# LM317.net
KiCad netlist of a schematic drawn in EAGLE
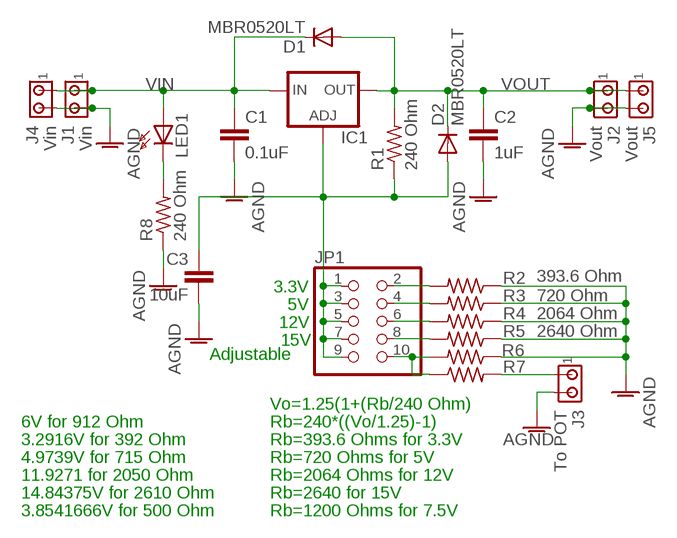
[diagram p0: schematic, sheet 1]

(export (version "E")
  (design (tool "Eeschema 10.0.6"))
  (components
    (comp (ref "C1")
      (value "0.1uF")
      (footprint "eagle-import:0805_PANASONIC")
      (libsource (lib "eagle-import") (part "0805_PANASONIC"))
    )
    (comp (ref "C2")
      (value "1uF")
      (footprint "eagle-import:0805_PANASONIC")
      (libsource (lib "eagle-import") (part "0805_PANASONIC"))
    )
    (comp (ref "C3")
      (value "10uF")
      (footprint "eagle-import:0805_PANASONIC")
      (libsource (lib "eagle-import") (part "0805_PANASONIC"))
    )
    (comp (ref "D1")
      (value "MBR0520LT")
      (footprint "eagle-import:SOD123")
      (libsource (lib "eagle-import") (part "MBR0520LT"))
    )
    (comp (ref "D2")
      (value "MBR0520LT")
      (footprint "eagle-import:SOD123")
      (libsource (lib "eagle-import") (part "MBR0520LT"))
    )
    (comp (ref "IC1")
      (value "LM317TS")
      (footprint "eagle-import:317TS")
      (libsource (lib "eagle-import") (part "LM317TS"))
    )
    (comp (ref "J1")
      (value "Vin")
      (footprint "eagle-import:640456-2")
      (libsource (lib "eagle-import") (part "AMP100640456-2"))
    )
    (comp (ref "J2")
      (value "Vout")
      (footprint "eagle-import:640456-2")
      (libsource (lib "eagle-import") (part "AMP100640456-2"))
    )
    (comp (ref "J3")
      (value "To POT")
      (footprint "eagle-import:640456-2")
      (libsource (lib "eagle-import") (part "AMP100640456-2"))
    )
    (comp (ref "J4")
      (value "Vin")
      (footprint "eagle-import:640456-2")
      (libsource (lib "eagle-import") (part "AMP100640456-2"))
    )
    (comp (ref "J5")
      (value "Vout")
      (footprint "eagle-import:640456-2")
      (libsource (lib "eagle-import") (part "AMP100640456-2"))
    )
    (comp (ref "JP1")
      (value "PINHD-2X5")
      (footprint "eagle-import:2X05")
      (libsource (lib "eagle-import") (part "PINHD-2X5"))
    )
    (comp (ref "LED1")
      (value "LED1206")
      (footprint "eagle-import:M1206")
      (libsource (lib "eagle-import") (part "LED1206"))
    )
    (comp (ref "R1")
      (value "240 Ohm")
      (footprint "eagle-import:0805_MARISS")
      (libsource (lib "eagle-import") (part "R_0805_MARISS"))
    )
    (comp (ref "R2")
      (value "393.6 Ohm")
      (footprint "eagle-import:0805_MARISS")
      (libsource (lib "eagle-import") (part "R_0805_MARISS"))
    )
    (comp (ref "R3")
      (value "720 Ohm")
      (footprint "eagle-import:0805_MARISS")
      (libsource (lib "eagle-import") (part "R_0805_MARISS"))
    )
    (comp (ref "R4")
      (value "2064 Ohm")
      (footprint "eagle-import:0805_MARISS")
      (libsource (lib "eagle-import") (part "R_0805_MARISS"))
    )
    (comp (ref "R5")
      (value "2640 Ohm")
      (footprint "eagle-import:0805_MARISS")
      (libsource (lib "eagle-import") (part "R_0805_MARISS"))
    )
    (comp (ref "R6")
      (value "R_0805_MARISS")
      (footprint "eagle-import:0805_MARISS")
      (libsource (lib "eagle-import") (part "R_0805_MARISS"))
    )
    (comp (ref "R7")
      (value "R_0805_MARISS")
      (footprint "eagle-import:0805_MARISS")
      (libsource (lib "eagle-import") (part "R_0805_MARISS"))
    )
    (comp (ref "R8")
      (value "240 Ohm")
      (footprint "eagle-import:0805_MARISS")
      (libsource (lib "eagle-import") (part "R_0805_MARISS"))
    )
  )
  (nets
    (net (code "1") (name "/VIN") (class "Default")
      (node (ref "C1") (pin "1") (pinfunction "1_1") (pintype "passive"))
      (node (ref "D1") (pin "C") (pinfunction "C_C") (pintype "passive"))
      (node (ref "IC1") (pin "3") (pinfunction "IN_3") (pintype "input"))
      (node (ref "J1") (pin "1") (pinfunction "1_1") (pintype "passive"))
      (node (ref "J4") (pin "1") (pinfunction "1_1") (pintype "passive"))
      (node (ref "LED1") (pin "1") (pinfunction "A_1") (pintype "passive"))
    )
    (net (code "2") (name "/VOUT") (class "Default")
      (node (ref "C2") (pin "1") (pinfunction "1_1") (pintype "passive"))
      (node (ref "D1") (pin "A") (pinfunction "A_A") (pintype "passive"))
      (node (ref "D2") (pin "C") (pinfunction "C_C") (pintype "passive"))
      (node (ref "IC1") (pin "2") (pinfunction "OUT_2") (pintype "passive"))
      (node (ref "J2") (pin "1") (pinfunction "1_1") (pintype "passive"))
      (node (ref "J5") (pin "1") (pinfunction "1_1") (pintype "passive"))
      (node (ref "R1") (pin "2") (pinfunction "2_2") (pintype "passive"))
    )
    (net (code "3") (name "AGND") (class "Default")
      (node (ref "C1") (pin "2") (pinfunction "2_2") (pintype "passive"))
      (node (ref "C2") (pin "2") (pinfunction "2_2") (pintype "passive"))
      (node (ref "C3") (pin "2") (pinfunction "2_2") (pintype "passive"))
      (node (ref "J1") (pin "2") (pinfunction "2_2") (pintype "passive"))
      (node (ref "J2") (pin "2") (pinfunction "2_2") (pintype "passive"))
      (node (ref "J3") (pin "2") (pinfunction "2_2") (pintype "passive"))
      (node (ref "J4") (pin "2") (pinfunction "2_2") (pintype "passive"))
      (node (ref "J5") (pin "2") (pinfunction "2_2") (pintype "passive"))
      (node (ref "R2") (pin "1") (pinfunction "1_1") (pintype "passive"))
      (node (ref "R3") (pin "1") (pinfunction "1_1") (pintype "passive"))
      (node (ref "R4") (pin "1") (pinfunction "1_1") (pintype "passive"))
      (node (ref "R5") (pin "1") (pinfunction "1_1") (pintype "passive"))
      (node (ref "R6") (pin "1") (pinfunction "1_1") (pintype "passive"))
      (node (ref "R8") (pin "1") (pinfunction "1_1") (pintype "passive"))
    )
    (net (code "4") (name "Net-(IC1-ADJ)") (class "Default")
      (node (ref "C3") (pin "1") (pinfunction "1_1") (pintype "passive"))
      (node (ref "D2") (pin "A") (pinfunction "A_A") (pintype "passive"))
      (node (ref "IC1") (pin "1") (pinfunction "ADJ_1") (pintype "input"))
      (node (ref "JP1") (pin "1") (pinfunction "1_1") (pintype "passive"))
      (node (ref "JP1") (pin "3") (pinfunction "3_3") (pintype "passive"))
      (node (ref "JP1") (pin "5") (pinfunction "5_5") (pintype "passive"))
      (node (ref "JP1") (pin "7") (pinfunction "7_7") (pintype "passive"))
      (node (ref "JP1") (pin "9") (pinfunction "9_9") (pintype "passive"))
      (node (ref "R1") (pin "1") (pinfunction "1_1") (pintype "passive"))
    )
    (net (code "5") (name "Net-(J3-Pad1)") (class "Default")
      (node (ref "J3") (pin "1") (pinfunction "1_1") (pintype "passive"))
      (node (ref "R7") (pin "2") (pinfunction "2_2") (pintype "passive"))
    )
    (net (code "6") (name "Net-(JP1-Pad2)") (class "Default")
      (node (ref "JP1") (pin "2") (pinfunction "2_2") (pintype "passive"))
      (node (ref "R2") (pin "2") (pinfunction "2_2") (pintype "passive"))
    )
    (net (code "7") (name "Net-(JP1-Pad4)") (class "Default")
      (node (ref "JP1") (pin "4") (pinfunction "4_4") (pintype "passive"))
      (node (ref "R3") (pin "2") (pinfunction "2_2") (pintype "passive"))
    )
    (net (code "8") (name "Net-(JP1-Pad6)") (class "Default")
      (node (ref "JP1") (pin "6") (pinfunction "6_6") (pintype "passive"))
      (node (ref "R4") (pin "2") (pinfunction "2_2") (pintype "passive"))
    )
    (net (code "9") (name "Net-(JP1-Pad8)") (class "Default")
      (node (ref "JP1") (pin "8") (pinfunction "8_8") (pintype "passive"))
      (node (ref "R5") (pin "2") (pinfunction "2_2") (pintype "passive"))
    )
    (net (code "10") (name "Net-(JP1-Pad10)") (class "Default")
      (node (ref "JP1") (pin "10") (pinfunction "10_10") (pintype "passive"))
      (node (ref "R6") (pin "2") (pinfunction "2_2") (pintype "passive"))
      (node (ref "R7") (pin "1") (pinfunction "1_1") (pintype "passive"))
    )
    (net (code "11") (name "Net-(LED1-C)") (class "Default")
      (node (ref "LED1") (pin "2") (pinfunction "C_2") (pintype "passive"))
      (node (ref "R8") (pin "2") (pinfunction "2_2") (pintype "passive"))
    )
  )
)
